# Board_760032.net
KiCad netlist of a schematic drawn in EAGLE
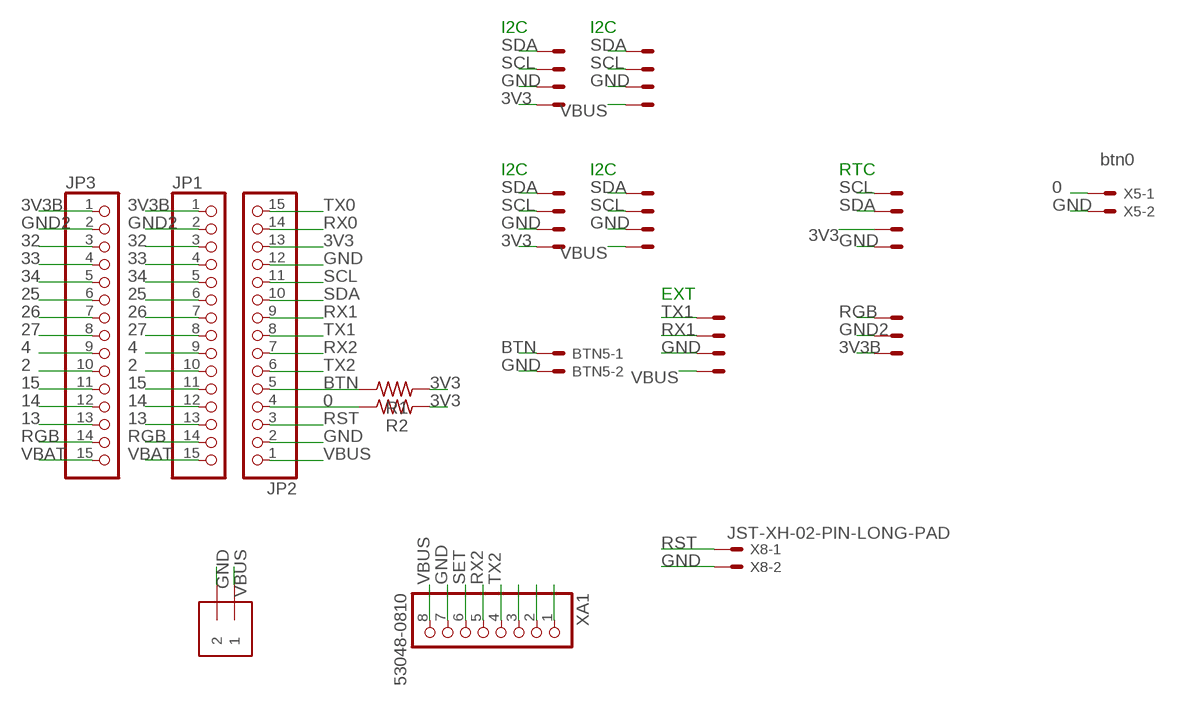
[diagram p0: schematic, sheet 1]

(export (version "E")
  (design (tool "Eeschema 10.0.6"))
  (components
    (comp (ref "BTN5")
      (value "JST-XH-02-PIN-LONG-PAD")
      (footprint "eagle-import:JST-XH-02-PACKAGE-LONG-PAD")
      (libsource (lib "eagle-import") (part "JST-XH-02-PIN-LONG-PAD"))
    )
    (comp (ref "J1")
      (value "1X2-3.5MM")
      (footprint "eagle-import:1X2-3.5MM")
      (libsource (lib "eagle-import") (part "1X2-3.5MM"))
    )
    (comp (ref "JP1")
      (value "PINHD-1X15")
      (footprint "eagle-import:1X15")
      (libsource (lib "eagle-import") (part "PINHD-1X15"))
    )
    (comp (ref "JP2")
      (value "PINHD-1X15")
      (footprint "eagle-import:1X15")
      (libsource (lib "eagle-import") (part "PINHD-1X15"))
    )
    (comp (ref "JP3")
      (value "PINHD-1X15")
      (footprint "eagle-import:1X15")
      (libsource (lib "eagle-import") (part "PINHD-1X15"))
    )
    (comp (ref "R1")
      (value "R-US_0207/7")
      (footprint "eagle-import:0207_7")
      (libsource (lib "eagle-import") (part "R-US_0207/7"))
    )
    (comp (ref "R2")
      (value "R-US_0207/7")
      (footprint "eagle-import:0207_7")
      (libsource (lib "eagle-import") (part "R-US_0207/7"))
    )
    (comp (ref "RTC")
      (value "JST-XH-04-PIN-LONG-PAD")
      (footprint "eagle-import:JST-XH-04-PACKAGE-LONG-PAD")
      (libsource (lib "eagle-import") (part "JST-XH-04-PIN-LONG-PAD"))
    )
    (comp (ref "X1")
      (value "JST-XH-04-PIN-LONG-PAD")
      (footprint "eagle-import:JST-XH-04-PACKAGE-LONG-PAD")
      (libsource (lib "eagle-import") (part "JST-XH-04-PIN-LONG-PAD"))
    )
    (comp (ref "X2")
      (value "JST-XH-04-PIN-LONG-PAD")
      (footprint "eagle-import:JST-XH-04-PACKAGE-LONG-PAD")
      (libsource (lib "eagle-import") (part "JST-XH-04-PIN-LONG-PAD"))
    )
    (comp (ref "X3")
      (value "JST-XH-04-PIN-LONG-PAD")
      (footprint "eagle-import:JST-XH-04-PACKAGE-LONG-PAD")
      (libsource (lib "eagle-import") (part "JST-XH-04-PIN-LONG-PAD"))
    )
    (comp (ref "X4")
      (value "JST-XH-03-PIN-LONG-PAD")
      (footprint "eagle-import:JST-XH-03-PACKAGE-LONG-PAD")
      (libsource (lib "eagle-import") (part "JST-XH-03-PIN-LONG-PAD"))
    )
    (comp (ref "X5")
      (value "btn0")
      (footprint "eagle-import:JST-XH-02-PACKAGE-LONG-PAD")
      (libsource (lib "eagle-import") (part "JST-XH-02-PIN-LONG-PAD"))
    )
    (comp (ref "X6")
      (value "JST-XH-04-PIN-LONG-PAD")
      (footprint "eagle-import:JST-XH-04-PACKAGE-LONG-PAD")
      (libsource (lib "eagle-import") (part "JST-XH-04-PIN-LONG-PAD"))
    )
    (comp (ref "X8")
      (value "JST-XH-02-PIN-LONG-PAD")
      (footprint "eagle-import:JST-XH-02-PACKAGE-LONG-PAD")
      (libsource (lib "eagle-import") (part "JST-XH-02-PIN-LONG-PAD"))
    )
    (comp (ref "X9")
      (value "JST-XH-04-PIN-LONG-PAD")
      (footprint "eagle-import:JST-XH-04-PACKAGE-LONG-PAD")
      (libsource (lib "eagle-import") (part "JST-XH-04-PIN-LONG-PAD"))
    )
    (comp (ref "XA1")
      (value "53048-0810")
      (footprint "eagle-import:MOLEX_53048-0810")
      (fields (field (name "MF") "Molex"))
      (libsource (lib "eagle-import") (part "53048-0810"))
    )
  )
  (nets
    (net (code "1") (name "/0") (class "Default")
      (node (ref "JP2") (pin "4") (pinfunction "4_4") (pintype "passive"))
      (node (ref "R2") (pin "1") (pinfunction "1_1") (pintype "passive"))
      (node (ref "X5") (pin "1") (pinfunction "S_1") (pintype "passive"))
    )
    (net (code "2") (name "/2") (class "Default")
      (node (ref "JP1") (pin "10") (pinfunction "10_10") (pintype "passive"))
      (node (ref "JP3") (pin "10") (pinfunction "10_10") (pintype "passive"))
    )
    (net (code "3") (name "/3V3") (class "Default")
      (node (ref "JP2") (pin "13") (pinfunction "13_13") (pintype "passive"))
      (node (ref "R1") (pin "2") (pinfunction "2_2") (pintype "passive"))
      (node (ref "R2") (pin "2") (pinfunction "2_2") (pintype "passive"))
      (node (ref "RTC") (pin "3") (pinfunction "S_3") (pintype "passive"))
      (node (ref "X1") (pin "4") (pinfunction "S_4") (pintype "passive"))
      (node (ref "X3") (pin "4") (pinfunction "S_4") (pintype "passive"))
    )
    (net (code "4") (name "/3V3B") (class "Default")
      (node (ref "JP1") (pin "1") (pinfunction "1_1") (pintype "passive"))
      (node (ref "JP3") (pin "1") (pinfunction "1_1") (pintype "passive"))
      (node (ref "X4") (pin "3") (pinfunction "S_3") (pintype "passive"))
    )
    (net (code "5") (name "/4") (class "Default")
      (node (ref "JP1") (pin "9") (pinfunction "9_9") (pintype "passive"))
      (node (ref "JP3") (pin "9") (pinfunction "9_9") (pintype "passive"))
    )
    (net (code "6") (name "/13") (class "Default")
      (node (ref "JP1") (pin "13") (pinfunction "13_13") (pintype "passive"))
      (node (ref "JP3") (pin "13") (pinfunction "13_13") (pintype "passive"))
    )
    (net (code "7") (name "/14") (class "Default")
      (node (ref "JP1") (pin "12") (pinfunction "12_12") (pintype "passive"))
      (node (ref "JP3") (pin "12") (pinfunction "12_12") (pintype "passive"))
    )
    (net (code "8") (name "/15") (class "Default")
      (node (ref "JP1") (pin "11") (pinfunction "11_11") (pintype "passive"))
      (node (ref "JP3") (pin "11") (pinfunction "11_11") (pintype "passive"))
    )
    (net (code "9") (name "/25") (class "Default")
      (node (ref "JP1") (pin "6") (pinfunction "6_6") (pintype "passive"))
      (node (ref "JP3") (pin "6") (pinfunction "6_6") (pintype "passive"))
    )
    (net (code "10") (name "/26") (class "Default")
      (node (ref "JP1") (pin "7") (pinfunction "7_7") (pintype "passive"))
      (node (ref "JP3") (pin "7") (pinfunction "7_7") (pintype "passive"))
    )
    (net (code "11") (name "/27") (class "Default")
      (node (ref "JP1") (pin "8") (pinfunction "8_8") (pintype "passive"))
      (node (ref "JP3") (pin "8") (pinfunction "8_8") (pintype "passive"))
    )
    (net (code "12") (name "/32") (class "Default")
      (node (ref "JP1") (pin "3") (pinfunction "3_3") (pintype "passive"))
      (node (ref "JP3") (pin "3") (pinfunction "3_3") (pintype "passive"))
    )
    (net (code "13") (name "/33") (class "Default")
      (node (ref "JP1") (pin "4") (pinfunction "4_4") (pintype "passive"))
      (node (ref "JP3") (pin "4") (pinfunction "4_4") (pintype "passive"))
    )
    (net (code "14") (name "/34") (class "Default")
      (node (ref "JP1") (pin "5") (pinfunction "5_5") (pintype "passive"))
      (node (ref "JP3") (pin "5") (pinfunction "5_5") (pintype "passive"))
    )
    (net (code "15") (name "/BTN") (class "Default")
      (node (ref "BTN5") (pin "1") (pinfunction "S_1") (pintype "passive"))
      (node (ref "JP2") (pin "5") (pinfunction "5_5") (pintype "passive"))
      (node (ref "R1") (pin "1") (pinfunction "1_1") (pintype "passive"))
    )
    (net (code "16") (name "/GND") (class "Default")
      (node (ref "BTN5") (pin "2") (pinfunction "S_2") (pintype "passive"))
      (node (ref "J1") (pin "2") (pinfunction "2_2") (pintype "passive"))
      (node (ref "JP2") (pin "12") (pinfunction "12_12") (pintype "passive"))
      (node (ref "JP2") (pin "2") (pinfunction "2_2") (pintype "passive"))
      (node (ref "RTC") (pin "4") (pinfunction "S_4") (pintype "passive"))
      (node (ref "X1") (pin "3") (pinfunction "S_3") (pintype "passive"))
      (node (ref "X2") (pin "3") (pinfunction "S_3") (pintype "passive"))
      (node (ref "X3") (pin "3") (pinfunction "S_3") (pintype "passive"))
      (node (ref "X5") (pin "2") (pinfunction "S_2") (pintype "passive"))
      (node (ref "X6") (pin "3") (pinfunction "S_3") (pintype "passive"))
      (node (ref "X8") (pin "2") (pinfunction "S_2") (pintype "passive"))
      (node (ref "X9") (pin "3") (pinfunction "S_3") (pintype "passive"))
      (node (ref "XA1") (pin "7") (pinfunction "7_7") (pintype "passive"))
    )
    (net (code "17") (name "/GND2") (class "Default")
      (node (ref "JP1") (pin "2") (pinfunction "2_2") (pintype "passive"))
      (node (ref "JP3") (pin "2") (pinfunction "2_2") (pintype "passive"))
      (node (ref "X4") (pin "2") (pinfunction "S_2") (pintype "passive"))
    )
    (net (code "18") (name "/RGB") (class "Default")
      (node (ref "JP1") (pin "14") (pinfunction "14_14") (pintype "passive"))
      (node (ref "JP3") (pin "14") (pinfunction "14_14") (pintype "passive"))
      (node (ref "X4") (pin "1") (pinfunction "S_1") (pintype "passive"))
    )
    (net (code "19") (name "/RST") (class "Default")
      (node (ref "JP2") (pin "3") (pinfunction "3_3") (pintype "passive"))
      (node (ref "X8") (pin "1") (pinfunction "S_1") (pintype "passive"))
    )
    (net (code "20") (name "/RX0") (class "Default")
      (node (ref "JP2") (pin "14") (pinfunction "14_14") (pintype "passive"))
    )
    (net (code "21") (name "/RX1") (class "Default")
      (node (ref "JP2") (pin "9") (pinfunction "9_9") (pintype "passive"))
      (node (ref "X6") (pin "2") (pinfunction "S_2") (pintype "passive"))
    )
    (net (code "22") (name "/RX2") (class "Default")
      (node (ref "JP2") (pin "7") (pinfunction "7_7") (pintype "passive"))
      (node (ref "XA1") (pin "5") (pinfunction "5_5") (pintype "passive"))
    )
    (net (code "23") (name "/SCL") (class "Default")
      (node (ref "JP2") (pin "11") (pinfunction "11_11") (pintype "passive"))
      (node (ref "RTC") (pin "1") (pinfunction "S_1") (pintype "passive"))
      (node (ref "X1") (pin "2") (pinfunction "S_2") (pintype "passive"))
      (node (ref "X2") (pin "2") (pinfunction "S_2") (pintype "passive"))
      (node (ref "X3") (pin "2") (pinfunction "S_2") (pintype "passive"))
      (node (ref "X9") (pin "2") (pinfunction "S_2") (pintype "passive"))
    )
    (net (code "24") (name "/SDA") (class "Default")
      (node (ref "JP2") (pin "10") (pinfunction "10_10") (pintype "passive"))
      (node (ref "RTC") (pin "2") (pinfunction "S_2") (pintype "passive"))
      (node (ref "X1") (pin "1") (pinfunction "S_1") (pintype "passive"))
      (node (ref "X2") (pin "1") (pinfunction "S_1") (pintype "passive"))
      (node (ref "X3") (pin "1") (pinfunction "S_1") (pintype "passive"))
      (node (ref "X9") (pin "1") (pinfunction "S_1") (pintype "passive"))
    )
    (net (code "25") (name "/SET") (class "Default")
      (node (ref "XA1") (pin "6") (pinfunction "6_6") (pintype "passive"))
    )
    (net (code "26") (name "/TX0") (class "Default")
      (node (ref "JP2") (pin "15") (pinfunction "15_15") (pintype "passive"))
    )
    (net (code "27") (name "/TX1") (class "Default")
      (node (ref "JP2") (pin "8") (pinfunction "8_8") (pintype "passive"))
      (node (ref "X6") (pin "1") (pinfunction "S_1") (pintype "passive"))
    )
    (net (code "28") (name "/TX2") (class "Default")
      (node (ref "JP2") (pin "6") (pinfunction "6_6") (pintype "passive"))
      (node (ref "XA1") (pin "4") (pinfunction "4_4") (pintype "passive"))
    )
    (net (code "29") (name "/VBAT") (class "Default")
      (node (ref "JP1") (pin "15") (pinfunction "15_15") (pintype "passive"))
      (node (ref "JP3") (pin "15") (pinfunction "15_15") (pintype "passive"))
    )
    (net (code "30") (name "/VBUS") (class "Default")
      (node (ref "J1") (pin "1") (pinfunction "1_1") (pintype "passive"))
      (node (ref "JP2") (pin "1") (pinfunction "1_1") (pintype "passive"))
      (node (ref "X2") (pin "4") (pinfunction "S_4") (pintype "passive"))
      (node (ref "X6") (pin "4") (pinfunction "S_4") (pintype "passive"))
      (node (ref "X9") (pin "4") (pinfunction "S_4") (pintype "passive"))
      (node (ref "XA1") (pin "8") (pinfunction "8_8") (pintype "passive"))
    )
    (net (code "31") (name "unconnected-(XA1-Pad1)") (class "Default")
      (node (ref "XA1") (pin "1") (pinfunction "1_1") (pintype "passive"))
    )
    (net (code "32") (name "unconnected-(XA1-Pad2)") (class "Default")
      (node (ref "XA1") (pin "2") (pinfunction "2_2") (pintype "passive"))
    )
    (net (code "33") (name "unconnected-(XA1-Pad3)") (class "Default")
      (node (ref "XA1") (pin "3") (pinfunction "3_3") (pintype "passive"))
    )
  )
)
